# DSDADC.net
KiCad netlist of a schematic drawn in Altium Designer
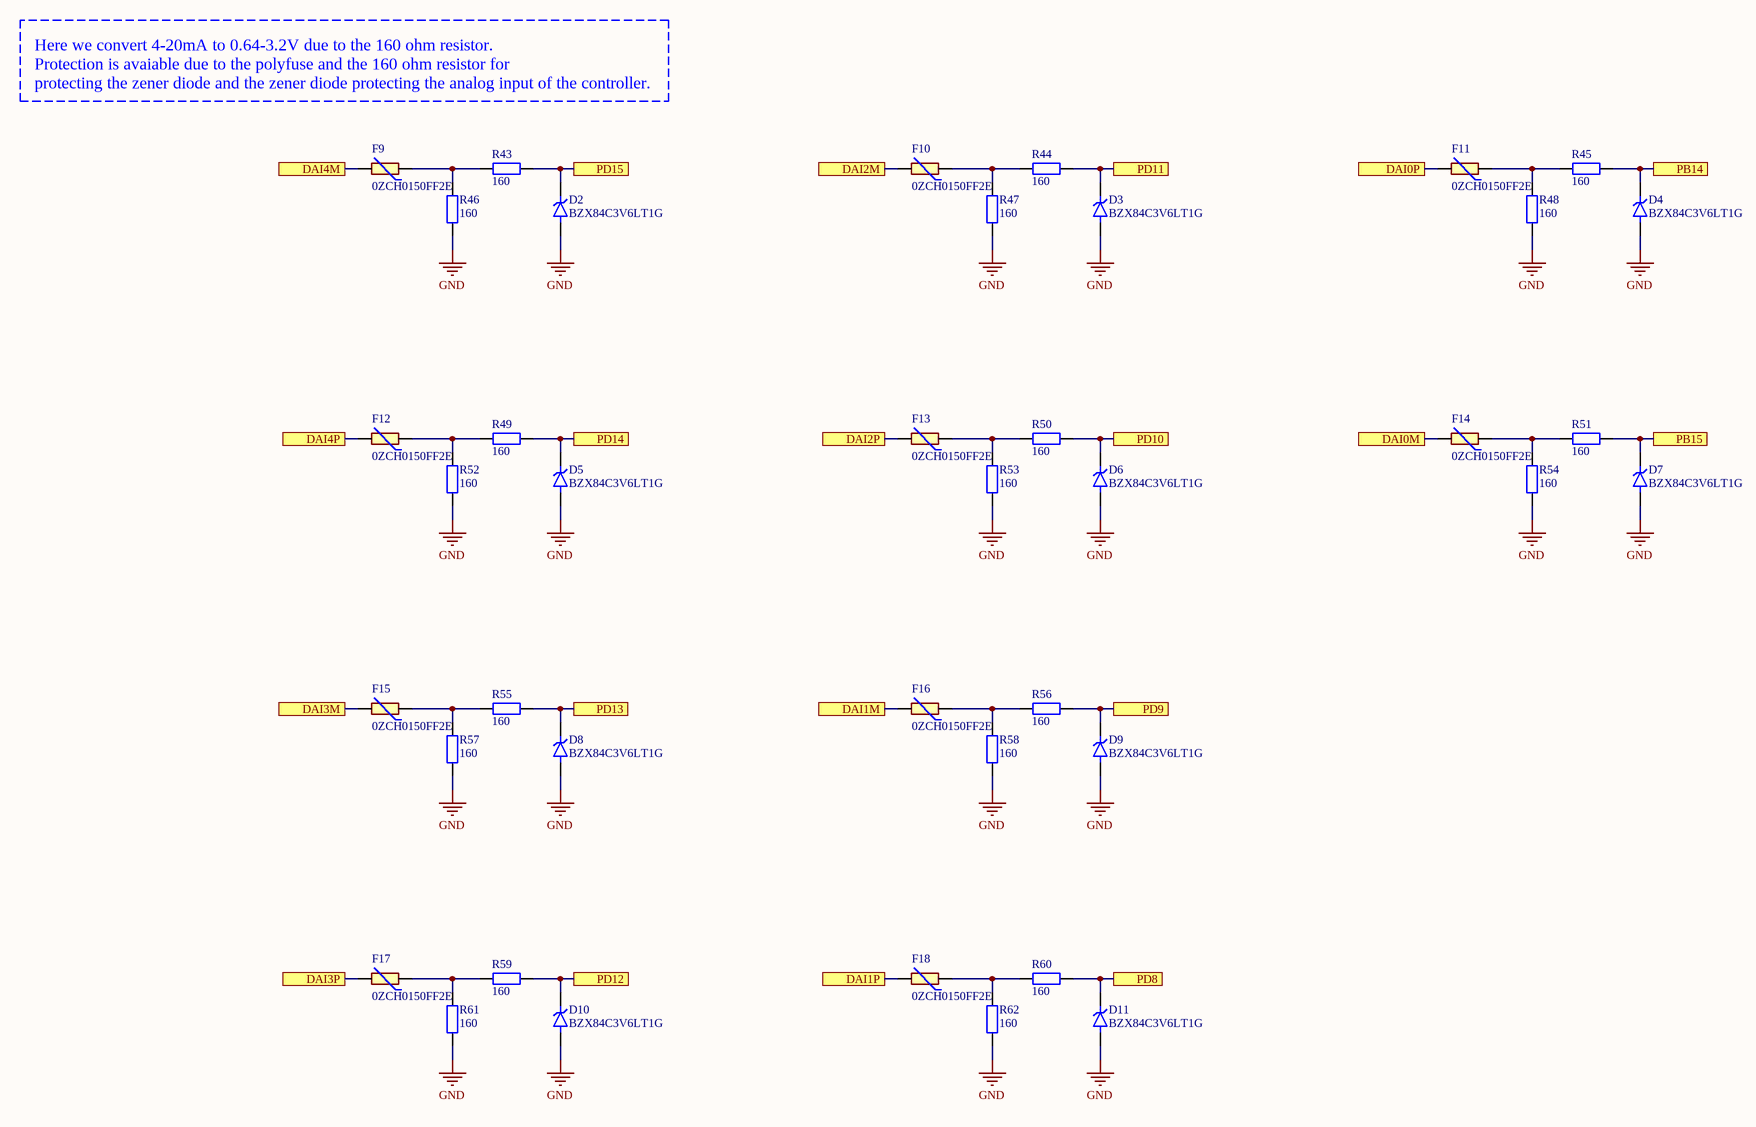
[diagram p0: DSDADC.SchDoc]

(export (version "E")
  (design (tool "Eeschema 10.0.6"))
  (components
    (comp (ref "D2")
      (value "BZX84C3V6LT1G")
      (footprint "SOT95P240X111-3N")
      (libsource (lib "BZX84C3V6LT1G") (part "BZX84C3V6LT1G"))
    )
    (comp (ref "D3")
      (value "BZX84C3V6LT1G")
      (footprint "SOT95P240X111-3N")
      (libsource (lib "BZX84C3V6LT1G") (part "BZX84C3V6LT1G"))
    )
    (comp (ref "D4")
      (value "BZX84C3V6LT1G")
      (footprint "SOT95P240X111-3N")
      (libsource (lib "BZX84C3V6LT1G") (part "BZX84C3V6LT1G"))
    )
    (comp (ref "D5")
      (value "BZX84C3V6LT1G")
      (footprint "SOT95P240X111-3N")
      (libsource (lib "BZX84C3V6LT1G") (part "BZX84C3V6LT1G"))
    )
    (comp (ref "D6")
      (value "BZX84C3V6LT1G")
      (footprint "SOT95P240X111-3N")
      (libsource (lib "BZX84C3V6LT1G") (part "BZX84C3V6LT1G"))
    )
    (comp (ref "D7")
      (value "BZX84C3V6LT1G")
      (footprint "SOT95P240X111-3N")
      (libsource (lib "BZX84C3V6LT1G") (part "BZX84C3V6LT1G"))
    )
    (comp (ref "D8")
      (value "BZX84C3V6LT1G")
      (footprint "SOT95P240X111-3N")
      (libsource (lib "BZX84C3V6LT1G") (part "BZX84C3V6LT1G"))
    )
    (comp (ref "D9")
      (value "BZX84C3V6LT1G")
      (footprint "SOT95P240X111-3N")
      (libsource (lib "BZX84C3V6LT1G") (part "BZX84C3V6LT1G"))
    )
    (comp (ref "D10")
      (value "BZX84C3V6LT1G")
      (footprint "SOT95P240X111-3N")
      (libsource (lib "BZX84C3V6LT1G") (part "BZX84C3V6LT1G"))
    )
    (comp (ref "D11")
      (value "BZX84C3V6LT1G")
      (footprint "SOT95P240X111-3N")
      (libsource (lib "BZX84C3V6LT1G") (part "BZX84C3V6LT1G"))
    )
    (comp (ref "F9")
      (value "0ZCH0150FF2E")
      (footprint "FUSC3225X90N")
      (description "1210 SMT PPTC ¦ 1.50 Ih ¦ 6V")
      (fields (field (name "MF") "Bel Fuse"))
      (libsource (lib "0ZCH0150FF2E") (part "0ZCH0150FF2E"))
    )
    (comp (ref "F10")
      (value "0ZCH0150FF2E")
      (footprint "FUSC3225X90N")
      (description "1210 SMT PPTC ¦ 1.50 Ih ¦ 6V")
      (fields (field (name "MF") "Bel Fuse"))
      (libsource (lib "0ZCH0150FF2E") (part "0ZCH0150FF2E"))
    )
    (comp (ref "F11")
      (value "0ZCH0150FF2E")
      (footprint "FUSC3225X90N")
      (description "1210 SMT PPTC ¦ 1.50 Ih ¦ 6V")
      (fields (field (name "MF") "Bel Fuse"))
      (libsource (lib "0ZCH0150FF2E") (part "0ZCH0150FF2E"))
    )
    (comp (ref "F12")
      (value "0ZCH0150FF2E")
      (footprint "FUSC3225X90N")
      (description "1210 SMT PPTC ¦ 1.50 Ih ¦ 6V")
      (fields (field (name "MF") "Bel Fuse"))
      (libsource (lib "0ZCH0150FF2E") (part "0ZCH0150FF2E"))
    )
    (comp (ref "F13")
      (value "0ZCH0150FF2E")
      (footprint "FUSC3225X90N")
      (description "1210 SMT PPTC ¦ 1.50 Ih ¦ 6V")
      (fields (field (name "MF") "Bel Fuse"))
      (libsource (lib "0ZCH0150FF2E") (part "0ZCH0150FF2E"))
    )
    (comp (ref "F14")
      (value "0ZCH0150FF2E")
      (footprint "FUSC3225X90N")
      (description "1210 SMT PPTC ¦ 1.50 Ih ¦ 6V")
      (fields (field (name "MF") "Bel Fuse"))
      (libsource (lib "0ZCH0150FF2E") (part "0ZCH0150FF2E"))
    )
    (comp (ref "F15")
      (value "0ZCH0150FF2E")
      (footprint "FUSC3225X90N")
      (description "1210 SMT PPTC ¦ 1.50 Ih ¦ 6V")
      (fields (field (name "MF") "Bel Fuse"))
      (libsource (lib "0ZCH0150FF2E") (part "0ZCH0150FF2E"))
    )
    (comp (ref "F16")
      (value "0ZCH0150FF2E")
      (footprint "FUSC3225X90N")
      (description "1210 SMT PPTC ¦ 1.50 Ih ¦ 6V")
      (fields (field (name "MF") "Bel Fuse"))
      (libsource (lib "0ZCH0150FF2E") (part "0ZCH0150FF2E"))
    )
    (comp (ref "F17")
      (value "0ZCH0150FF2E")
      (footprint "FUSC3225X90N")
      (description "1210 SMT PPTC ¦ 1.50 Ih ¦ 6V")
      (fields (field (name "MF") "Bel Fuse"))
      (libsource (lib "0ZCH0150FF2E") (part "0ZCH0150FF2E"))
    )
    (comp (ref "F18")
      (value "0ZCH0150FF2E")
      (footprint "FUSC3225X90N")
      (description "1210 SMT PPTC ¦ 1.50 Ih ¦ 6V")
      (fields (field (name "MF") "Bel Fuse"))
      (libsource (lib "0ZCH0150FF2E") (part "0ZCH0150FF2E"))
    )
    (comp (ref "R43")
      (value "160")
      (footprint "tro smd 0603")
      (description "RES")
      (libsource (lib "AUSB") (part "Tro 0603 1% 10k"))
    )
    (comp (ref "R44")
      (value "160")
      (footprint "tro smd 0603")
      (description "RES")
      (libsource (lib "AUSB") (part "Tro 0603 1% 10k"))
    )
    (comp (ref "R45")
      (value "160")
      (footprint "tro smd 0603")
      (description "RES")
      (libsource (lib "AUSB") (part "Tro 0603 1% 10k"))
    )
    (comp (ref "R46")
      (value "160")
      (footprint "tro smd 0603")
      (description "RES")
      (libsource (lib "AUSB") (part "Tro 0603 1% 10k"))
    )
    (comp (ref "R47")
      (value "160")
      (footprint "tro smd 0603")
      (description "RES")
      (libsource (lib "AUSB") (part "Tro 0603 1% 10k"))
    )
    (comp (ref "R48")
      (value "160")
      (footprint "tro smd 0603")
      (description "RES")
      (libsource (lib "AUSB") (part "Tro 0603 1% 10k"))
    )
    (comp (ref "R49")
      (value "160")
      (footprint "tro smd 0603")
      (description "RES")
      (libsource (lib "AUSB") (part "Tro 0603 1% 10k"))
    )
    (comp (ref "R50")
      (value "160")
      (footprint "tro smd 0603")
      (description "RES")
      (libsource (lib "AUSB") (part "Tro 0603 1% 10k"))
    )
    (comp (ref "R51")
      (value "160")
      (footprint "tro smd 0603")
      (description "RES")
      (libsource (lib "AUSB") (part "Tro 0603 1% 10k"))
    )
    (comp (ref "R52")
      (value "160")
      (footprint "tro smd 0603")
      (description "RES")
      (libsource (lib "AUSB") (part "Tro 0603 1% 10k"))
    )
    (comp (ref "R53")
      (value "160")
      (footprint "tro smd 0603")
      (description "RES")
      (libsource (lib "AUSB") (part "Tro 0603 1% 10k"))
    )
    (comp (ref "R54")
      (value "160")
      (footprint "tro smd 0603")
      (description "RES")
      (libsource (lib "AUSB") (part "Tro 0603 1% 10k"))
    )
    (comp (ref "R55")
      (value "160")
      (footprint "tro smd 0603")
      (description "RES")
      (libsource (lib "AUSB") (part "Tro 0603 1% 10k"))
    )
    (comp (ref "R56")
      (value "160")
      (footprint "tro smd 0603")
      (description "RES")
      (libsource (lib "AUSB") (part "Tro 0603 1% 10k"))
    )
    (comp (ref "R57")
      (value "160")
      (footprint "tro smd 0603")
      (description "RES")
      (libsource (lib "AUSB") (part "Tro 0603 1% 10k"))
    )
    (comp (ref "R58")
      (value "160")
      (footprint "tro smd 0603")
      (description "RES")
      (libsource (lib "AUSB") (part "Tro 0603 1% 10k"))
    )
    (comp (ref "R59")
      (value "160")
      (footprint "tro smd 0603")
      (description "RES")
      (libsource (lib "AUSB") (part "Tro 0603 1% 10k"))
    )
    (comp (ref "R60")
      (value "160")
      (footprint "tro smd 0603")
      (description "RES")
      (libsource (lib "AUSB") (part "Tro 0603 1% 10k"))
    )
    (comp (ref "R61")
      (value "160")
      (footprint "tro smd 0603")
      (description "RES")
      (libsource (lib "AUSB") (part "Tro 0603 1% 10k"))
    )
    (comp (ref "R62")
      (value "160")
      (footprint "tro smd 0603")
      (description "RES")
      (libsource (lib "AUSB") (part "Tro 0603 1% 10k"))
    )
  )
  (nets
    (net (code "1") (name "/DAI0M") (class "Default")
      (node (ref "F14") (pin "2") (pinfunction "2_2") (pintype "passive"))
    )
    (net (code "2") (name "/DAI0P") (class "Default")
      (node (ref "F11") (pin "2") (pinfunction "2_2") (pintype "passive"))
    )
    (net (code "3") (name "/DAI1M") (class "Default")
      (node (ref "F16") (pin "2") (pinfunction "2_2") (pintype "passive"))
    )
    (net (code "4") (name "/DAI1P") (class "Default")
      (node (ref "F18") (pin "2") (pinfunction "2_2") (pintype "passive"))
    )
    (net (code "5") (name "/DAI2M") (class "Default")
      (node (ref "F10") (pin "2") (pinfunction "2_2") (pintype "passive"))
    )
    (net (code "6") (name "/DAI2P") (class "Default")
      (node (ref "F13") (pin "2") (pinfunction "2_2") (pintype "passive"))
    )
    (net (code "7") (name "/DAI3M") (class "Default")
      (node (ref "F15") (pin "2") (pinfunction "2_2") (pintype "passive"))
    )
    (net (code "8") (name "/DAI3P") (class "Default")
      (node (ref "F17") (pin "2") (pinfunction "2_2") (pintype "passive"))
    )
    (net (code "9") (name "/DAI4M") (class "Default")
      (node (ref "F9") (pin "2") (pinfunction "2_2") (pintype "passive"))
    )
    (net (code "10") (name "/DAI4P") (class "Default")
      (node (ref "F12") (pin "2") (pinfunction "2_2") (pintype "passive"))
    )
    (net (code "11") (name "/PB14") (class "Default")
      (node (ref "D4") (pin "3") (pinfunction "K_3") (pintype "passive"))
      (node (ref "R45") (pin "2") (pinfunction "2_2") (pintype "passive"))
    )
    (net (code "12") (name "/PB15") (class "Default")
      (node (ref "D7") (pin "3") (pinfunction "K_3") (pintype "passive"))
      (node (ref "R51") (pin "2") (pinfunction "2_2") (pintype "passive"))
    )
    (net (code "13") (name "/PD8") (class "Default")
      (node (ref "D11") (pin "3") (pinfunction "K_3") (pintype "passive"))
      (node (ref "R60") (pin "2") (pinfunction "2_2") (pintype "passive"))
    )
    (net (code "14") (name "/PD9") (class "Default")
      (node (ref "D9") (pin "3") (pinfunction "K_3") (pintype "passive"))
      (node (ref "R56") (pin "2") (pinfunction "2_2") (pintype "passive"))
    )
    (net (code "15") (name "/PD10") (class "Default")
      (node (ref "D6") (pin "3") (pinfunction "K_3") (pintype "passive"))
      (node (ref "R50") (pin "2") (pinfunction "2_2") (pintype "passive"))
    )
    (net (code "16") (name "/PD11") (class "Default")
      (node (ref "D3") (pin "3") (pinfunction "K_3") (pintype "passive"))
      (node (ref "R44") (pin "2") (pinfunction "2_2") (pintype "passive"))
    )
    (net (code "17") (name "/PD12") (class "Default")
      (node (ref "D10") (pin "3") (pinfunction "K_3") (pintype "passive"))
      (node (ref "R59") (pin "2") (pinfunction "2_2") (pintype "passive"))
    )
    (net (code "18") (name "/PD13") (class "Default")
      (node (ref "D8") (pin "3") (pinfunction "K_3") (pintype "passive"))
      (node (ref "R55") (pin "2") (pinfunction "2_2") (pintype "passive"))
    )
    (net (code "19") (name "/PD14") (class "Default")
      (node (ref "D5") (pin "3") (pinfunction "K_3") (pintype "passive"))
      (node (ref "R49") (pin "2") (pinfunction "2_2") (pintype "passive"))
    )
    (net (code "20") (name "/PD15") (class "Default")
      (node (ref "D2") (pin "3") (pinfunction "K_3") (pintype "passive"))
      (node (ref "R43") (pin "2") (pinfunction "2_2") (pintype "passive"))
    )
    (net (code "21") (name "GND") (class "Default")
      (node (ref "D10") (pin "1") (pinfunction "A_1") (pintype "passive"))
      (node (ref "D11") (pin "1") (pinfunction "A_1") (pintype "passive"))
      (node (ref "D2") (pin "1") (pinfunction "A_1") (pintype "passive"))
      (node (ref "D3") (pin "1") (pinfunction "A_1") (pintype "passive"))
      (node (ref "D4") (pin "1") (pinfunction "A_1") (pintype "passive"))
      (node (ref "D5") (pin "1") (pinfunction "A_1") (pintype "passive"))
      (node (ref "D6") (pin "1") (pinfunction "A_1") (pintype "passive"))
      (node (ref "D7") (pin "1") (pinfunction "A_1") (pintype "passive"))
      (node (ref "D8") (pin "1") (pinfunction "A_1") (pintype "passive"))
      (node (ref "D9") (pin "1") (pinfunction "A_1") (pintype "passive"))
      (node (ref "R46") (pin "1") (pinfunction "1_1") (pintype "passive"))
      (node (ref "R47") (pin "1") (pinfunction "1_1") (pintype "passive"))
      (node (ref "R48") (pin "1") (pinfunction "1_1") (pintype "passive"))
      (node (ref "R52") (pin "1") (pinfunction "1_1") (pintype "passive"))
      (node (ref "R53") (pin "1") (pinfunction "1_1") (pintype "passive"))
      (node (ref "R54") (pin "1") (pinfunction "1_1") (pintype "passive"))
      (node (ref "R57") (pin "1") (pinfunction "1_1") (pintype "passive"))
      (node (ref "R58") (pin "1") (pinfunction "1_1") (pintype "passive"))
      (node (ref "R61") (pin "1") (pinfunction "1_1") (pintype "passive"))
      (node (ref "R62") (pin "1") (pinfunction "1_1") (pintype "passive"))
    )
    (net (code "22") (name "Net-(F9-Pad1)") (class "Default")
      (node (ref "F9") (pin "1") (pinfunction "1_1") (pintype "passive"))
      (node (ref "R43") (pin "1") (pinfunction "1_1") (pintype "passive"))
      (node (ref "R46") (pin "2") (pinfunction "2_2") (pintype "passive"))
    )
    (net (code "23") (name "Net-(F10-Pad1)") (class "Default")
      (node (ref "F10") (pin "1") (pinfunction "1_1") (pintype "passive"))
      (node (ref "R44") (pin "1") (pinfunction "1_1") (pintype "passive"))
      (node (ref "R47") (pin "2") (pinfunction "2_2") (pintype "passive"))
    )
    (net (code "24") (name "Net-(F11-Pad1)") (class "Default")
      (node (ref "F11") (pin "1") (pinfunction "1_1") (pintype "passive"))
      (node (ref "R45") (pin "1") (pinfunction "1_1") (pintype "passive"))
      (node (ref "R48") (pin "2") (pinfunction "2_2") (pintype "passive"))
    )
    (net (code "25") (name "Net-(F12-Pad1)") (class "Default")
      (node (ref "F12") (pin "1") (pinfunction "1_1") (pintype "passive"))
      (node (ref "R49") (pin "1") (pinfunction "1_1") (pintype "passive"))
      (node (ref "R52") (pin "2") (pinfunction "2_2") (pintype "passive"))
    )
    (net (code "26") (name "Net-(F13-Pad1)") (class "Default")
      (node (ref "F13") (pin "1") (pinfunction "1_1") (pintype "passive"))
      (node (ref "R50") (pin "1") (pinfunction "1_1") (pintype "passive"))
      (node (ref "R53") (pin "2") (pinfunction "2_2") (pintype "passive"))
    )
    (net (code "27") (name "Net-(F14-Pad1)") (class "Default")
      (node (ref "F14") (pin "1") (pinfunction "1_1") (pintype "passive"))
      (node (ref "R51") (pin "1") (pinfunction "1_1") (pintype "passive"))
      (node (ref "R54") (pin "2") (pinfunction "2_2") (pintype "passive"))
    )
    (net (code "28") (name "Net-(F15-Pad1)") (class "Default")
      (node (ref "F15") (pin "1") (pinfunction "1_1") (pintype "passive"))
      (node (ref "R55") (pin "1") (pinfunction "1_1") (pintype "passive"))
      (node (ref "R57") (pin "2") (pinfunction "2_2") (pintype "passive"))
    )
    (net (code "29") (name "Net-(F16-Pad1)") (class "Default")
      (node (ref "F16") (pin "1") (pinfunction "1_1") (pintype "passive"))
      (node (ref "R56") (pin "1") (pinfunction "1_1") (pintype "passive"))
      (node (ref "R58") (pin "2") (pinfunction "2_2") (pintype "passive"))
    )
    (net (code "30") (name "Net-(F17-Pad1)") (class "Default")
      (node (ref "F17") (pin "1") (pinfunction "1_1") (pintype "passive"))
      (node (ref "R59") (pin "1") (pinfunction "1_1") (pintype "passive"))
      (node (ref "R61") (pin "2") (pinfunction "2_2") (pintype "passive"))
    )
    (net (code "31") (name "Net-(F18-Pad1)") (class "Default")
      (node (ref "F18") (pin "1") (pinfunction "1_1") (pintype "passive"))
      (node (ref "R60") (pin "1") (pinfunction "1_1") (pintype "passive"))
      (node (ref "R62") (pin "2") (pinfunction "2_2") (pintype "passive"))
    )
  )
)
